# test1.net
KiCad netlist of a schematic drawn in Altium Designer
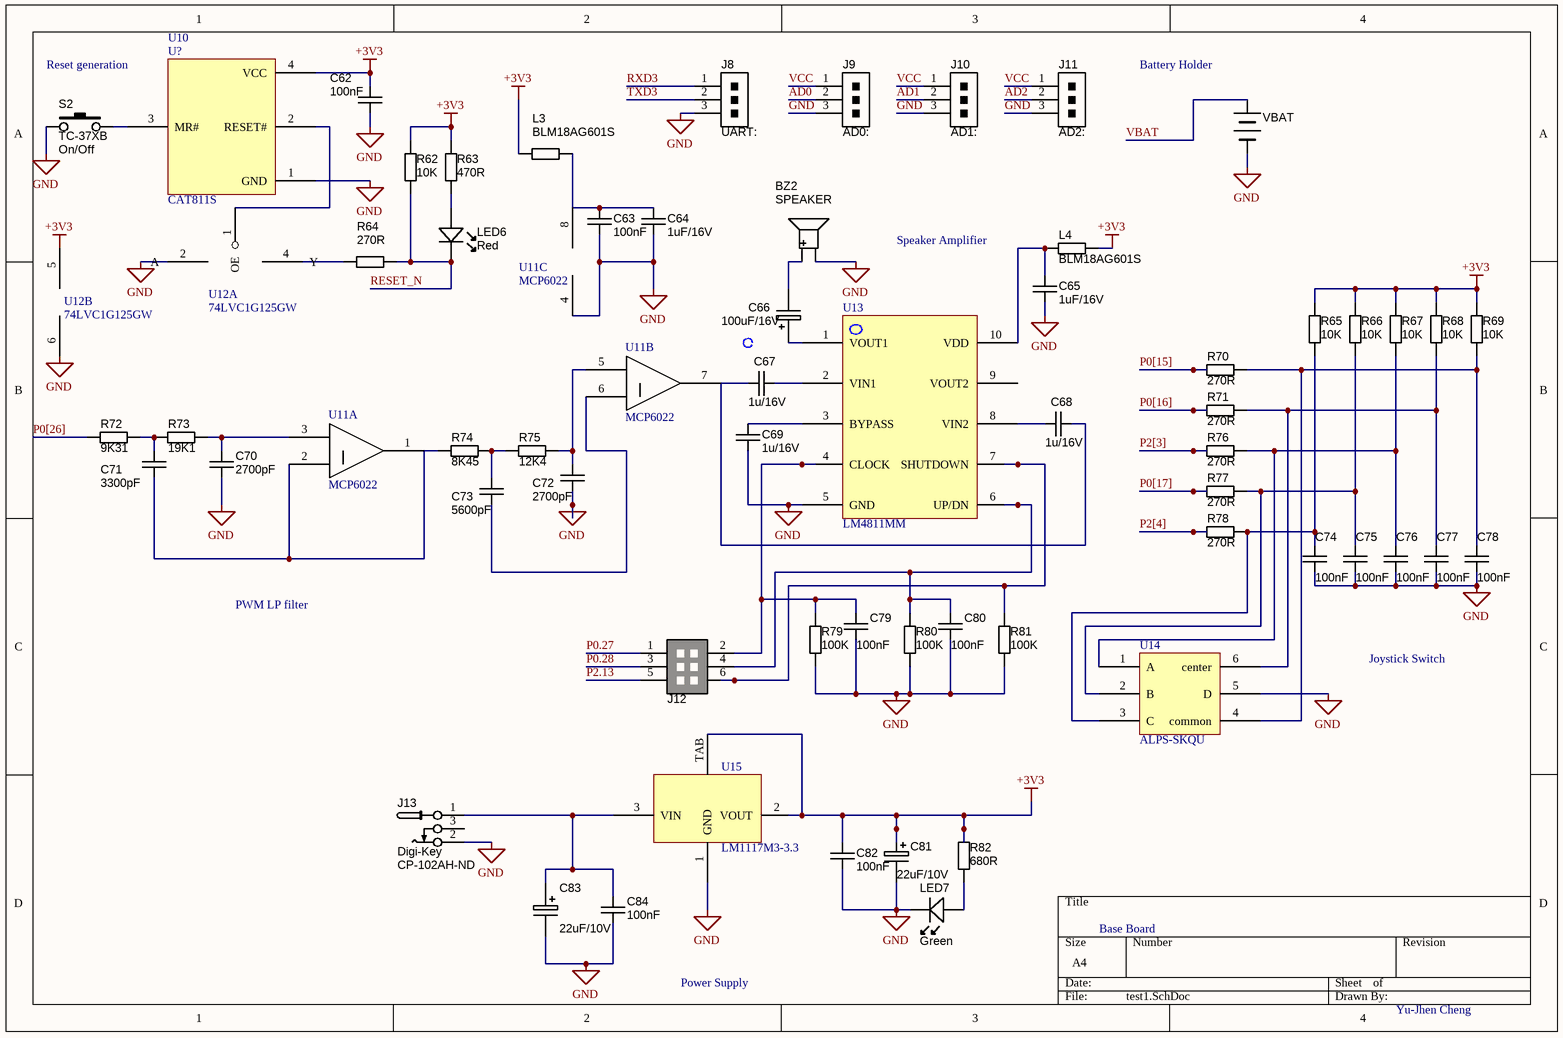
[diagram p0: test1.SchDoc]

(export (version "E")
  (design (tool "Eeschema 10.0.6"))
  (components
    (comp (ref "BZ2")
      (value "Alternate part: 3100-932")
      (footprint "BUZZER_12.0X8.5MM")
      (description "Speaker, Magnetic Transducer")
      (fields (field (name "MANUFACTURER PART NUMBER 1") "SPEAKER"))
      (libsource (lib "PBL - Electromechanical") (part "BZ_12x8.5x6.5_2kHz"))
    )
    (comp (ref "C62")
      (value "100nF")
      (footprint "CAPC2012N")
      (description "Capacitor SMD Cer 100nF 10% 50V X7R 0805")
      (fields (field (name "TOLERANCE") "?0%") (field (name "Comment") "approved sub OK"))
      (libsource (lib "PBL - Capacitors") (part "CAPC_100n_0805"))
    )
    (comp (ref "C63")
      (value "100nF")
      (footprint "CAPC2012N")
      (description "Capacitor SMD Cer 100nF 10% 50V X7R 0805")
      (fields (field (name "TOLERANCE") "?0%") (field (name "Comment") "approved sub OK"))
      (libsource (lib "PBL - Capacitors") (part "CAPC_100n_0805"))
    )
    (comp (ref "C64")
      (value "1uF/16V")
      (footprint "CAPC2012N")
      (description "Capacitor SMD Cer 100nF 10% 50V X7R 0805")
      (fields (field (name "TOLERANCE") "?0%") (field (name "Comment") "approved sub OK"))
      (libsource (lib "PBL - Capacitors") (part "CAPC_100n_0805"))
    )
    (comp (ref "C65")
      (value "1uF/16V")
      (footprint "CAPC2012N")
      (description "Capacitor SMD Cer 100nF 10% 50V X7R 0805")
      (fields (field (name "TOLERANCE") "?0%") (field (name "Comment") "approved sub OK"))
      (libsource (lib "PBL - Capacitors") (part "CAPC_100n_0805"))
    )
    (comp (ref "C66")
      (value "~")
      (footprint "CAPMP3528X210N")
      (description "Capacitor SMD Tantalum 100uF 20% 6.3V 1210")
      (fields (field (name "TOLERANCE") "?0%") (field (name "ALTIUM_UNNAMED_1") "100uF/16V"))
      (libsource (lib "PBL - Capacitors") (part "CAPT_100u_1210_6V3"))
    )
    (comp (ref "C67")
      (value "1u/16V")
      (footprint "CAPC2012N")
      (description "Capacitor SMD Cer 100nF 10% 50V X7R 0805")
      (fields (field (name "TOLERANCE") "?0%") (field (name "Comment") "approved sub OK"))
      (libsource (lib "PBL - Capacitors") (part "CAPC_100n_0805"))
    )
    (comp (ref "C68")
      (value "1u/16V")
      (footprint "CAPC2012N")
      (description "Capacitor SMD Cer 100nF 10% 50V X7R 0805")
      (fields (field (name "TOLERANCE") "?0%") (field (name "Comment") "approved sub OK"))
      (libsource (lib "PBL - Capacitors") (part "CAPC_100n_0805"))
    )
    (comp (ref "C69")
      (value "1u/16V")
      (footprint "CAPC2012N")
      (description "Capacitor SMD Cer 100nF 10% 50V X7R 0805")
      (fields (field (name "TOLERANCE") "?0%") (field (name "Comment") "approved sub OK"))
      (libsource (lib "PBL - Capacitors") (part "CAPC_100n_0805"))
    )
    (comp (ref "C70")
      (value "2700pF")
      (footprint "CAPC2012N")
      (description "Capacitor SMD Cer 100nF 10% 50V X7R 0805")
      (fields (field (name "TOLERANCE") "?0%") (field (name "Comment") "approved sub OK"))
      (libsource (lib "PBL - Capacitors") (part "CAPC_100n_0805"))
    )
    (comp (ref "C71")
      (value "3300pF")
      (footprint "CAPC2012N")
      (description "Capacitor SMD Cer 100nF 10% 50V X7R 0805")
      (fields (field (name "TOLERANCE") "?0%") (field (name "Comment") "approved sub OK"))
      (libsource (lib "PBL - Capacitors") (part "CAPC_100n_0805"))
    )
    (comp (ref "C72")
      (value "2700pF")
      (footprint "CAPC2012N")
      (description "Capacitor SMD Cer 100nF 10% 50V X7R 0805")
      (fields (field (name "TOLERANCE") "?0%") (field (name "Comment") "approved sub OK"))
      (libsource (lib "PBL - Capacitors") (part "CAPC_100n_0805"))
    )
    (comp (ref "C73")
      (value "5600pF")
      (footprint "CAPC2012N")
      (description "Capacitor SMD Cer 100nF 10% 50V X7R 0805")
      (fields (field (name "TOLERANCE") "?0%") (field (name "Comment") "approved sub OK"))
      (libsource (lib "PBL - Capacitors") (part "CAPC_100n_0805"))
    )
    (comp (ref "C74")
      (value "100nF")
      (footprint "CAPC2012N")
      (description "Capacitor SMD Cer 100nF 10% 50V X7R 0805")
      (fields (field (name "TOLERANCE") "?0%") (field (name "Comment") "approved sub OK"))
      (libsource (lib "PBL - Capacitors") (part "CAPC_100n_0805"))
    )
    (comp (ref "C75")
      (value "100nF")
      (footprint "CAPC2012N")
      (description "Capacitor SMD Cer 100nF 10% 50V X7R 0805")
      (fields (field (name "TOLERANCE") "?0%") (field (name "Comment") "approved sub OK"))
      (libsource (lib "PBL - Capacitors") (part "CAPC_100n_0805"))
    )
    (comp (ref "C76")
      (value "100nF")
      (footprint "CAPC2012N")
      (description "Capacitor SMD Cer 100nF 10% 50V X7R 0805")
      (fields (field (name "TOLERANCE") "?0%") (field (name "Comment") "approved sub OK"))
      (libsource (lib "PBL - Capacitors") (part "CAPC_100n_0805"))
    )
    (comp (ref "C77")
      (value "100nF")
      (footprint "CAPC2012N")
      (description "Capacitor SMD Cer 100nF 10% 50V X7R 0805")
      (fields (field (name "TOLERANCE") "?0%") (field (name "Comment") "approved sub OK"))
      (libsource (lib "PBL - Capacitors") (part "CAPC_100n_0805"))
    )
    (comp (ref "C78")
      (value "100nF")
      (footprint "CAPC2012N")
      (description "Capacitor SMD Cer 100nF 10% 50V X7R 0805")
      (fields (field (name "TOLERANCE") "?0%") (field (name "Comment") "approved sub OK"))
      (libsource (lib "PBL - Capacitors") (part "CAPC_100n_0805"))
    )
    (comp (ref "C79")
      (value "100nF")
      (footprint "CAPC2012N")
      (description "Capacitor SMD Cer 100nF 10% 50V X7R 0805")
      (fields (field (name "TOLERANCE") "?0%") (field (name "Comment") "approved sub OK"))
      (libsource (lib "PBL - Capacitors") (part "CAPC_100n_0805"))
    )
    (comp (ref "C80")
      (value "100nF")
      (footprint "CAPC2012N")
      (description "Capacitor SMD Cer 100nF 10% 50V X7R 0805")
      (fields (field (name "TOLERANCE") "?0%") (field (name "Comment") "approved sub OK"))
      (libsource (lib "PBL - Capacitors") (part "CAPC_100n_0805"))
    )
    (comp (ref "C81")
      (value "~")
      (footprint "CAPMP3528X210N")
      (description "Capacitor SMD Tantalum 100uF 20% 6.3V 1210")
      (fields (field (name "TOLERANCE") "?0%") (field (name "ALTIUM_UNNAMED_1") "22uF/10V"))
      (libsource (lib "PBL - Capacitors") (part "CAPT_100u_1210_6V3"))
    )
    (comp (ref "C82")
      (value "100nF")
      (footprint "CAPC2012N")
      (description "Capacitor SMD Cer 100nF 10% 50V X7R 0805")
      (fields (field (name "TOLERANCE") "?0%") (field (name "Comment") "approved sub OK"))
      (libsource (lib "PBL - Capacitors") (part "CAPC_100n_0805"))
    )
    (comp (ref "C83")
      (value "~")
      (footprint "CAPMP3528X210N")
      (description "Capacitor SMD Tantalum 100uF 20% 6.3V 1210")
      (fields (field (name "TOLERANCE") "?0%") (field (name "ALTIUM_UNNAMED_1") "22uF/10V"))
      (libsource (lib "PBL - Capacitors") (part "CAPT_100u_1210_6V3"))
    )
    (comp (ref "C84")
      (value "100nF")
      (footprint "CAPC2012N")
      (description "Capacitor SMD Cer 100nF 10% 50V X7R 0805")
      (fields (field (name "TOLERANCE") "?0%") (field (name "Comment") "approved sub OK"))
      (libsource (lib "PBL - Capacitors") (part "CAPC_100n_0805"))
    )
    (comp (ref "J8")
      (value "CONN_HEADER_1x3P_0.100in")
      (footprint "1x3POS_HEADER")
      (description "Pin Header, THT, Single-row, 2.54mm pitch")
      (libsource (lib "PBL - Connectors") (part "CONN_HEADER_1x3P_0.100in"))
    )
    (comp (ref "J9")
      (value "CONN_HEADER_1x3P_0.100in")
      (footprint "1x3POS_HEADER")
      (description "Pin Header, THT, Single-row, 2.54mm pitch")
      (libsource (lib "PBL - Connectors") (part "CONN_HEADER_1x3P_0.100in"))
    )
    (comp (ref "J10")
      (value "CONN_HEADER_1x3P_0.100in")
      (footprint "1x3POS_HEADER")
      (description "Pin Header, THT, Single-row, 2.54mm pitch")
      (libsource (lib "PBL - Connectors") (part "CONN_HEADER_1x3P_0.100in"))
    )
    (comp (ref "J11")
      (value "CONN_HEADER_1x3P_0.100in")
      (footprint "1x3POS_HEADER")
      (description "Pin Header, THT, Single-row, 2.54mm pitch")
      (libsource (lib "PBL - Connectors") (part "CONN_HEADER_1x3P_0.100in"))
    )
    (comp (ref "J12")
      (value "micro-match socket")
      (footprint "6P_PCB_SOCKET_BRD_MNT_MICRO-MATCH")
      (description "Socket THD 6 POS Double-row 2.54mm pitch")
      (libsource (lib "PBL - Connectors") (part "CONN_SOCKET_2x3P_0.100in_Female"))
    )
    (comp (ref "J13")
      (value "CONN_PWR_JACK_2.1x5.5mm")
      (footprint "CONN_PWR_JACK_2.1x5.5mm")
      (description "Power Connector, THT, 2.1mm ID, 5.5mm OD")
      (fields (field (name "SUPPLIER 1") "Digi-Key") (field (name "SUPPLIER PART NUMBER 1") "CP-102AH-ND"))
      (libsource (lib "PBL - Connectors") (part "CONN_PWR_JACK_2.1x5.5mm"))
    )
    (comp (ref "L3")
      (value "BLM18AG601S")
      (footprint "RESC2012N")
      (description "Resistor SMD chip 10k Ohm 0.125W 5% 0805")
      (fields (field (name "TOLERANCE") "?%") (field (name "Comment") "Thick Film"))
      (libsource (lib "") (part "RES_10K_0805_5%_1"))
    )
    (comp (ref "L4")
      (value "BLM18AG601S")
      (footprint "RESC2012N")
      (description "Resistor SMD chip 10k Ohm 0.125W 5% 0805")
      (fields (field (name "TOLERANCE") "?%") (field (name "Comment") "Thick Film"))
      (libsource (lib "") (part "RES_10K_0805_5%_1"))
    )
    (comp (ref "LED6")
      (value "Red")
      (footprint "LED-0805-A")
      (description "LED, 0805 SMD, Red")
      (libsource (lib "PBL - Light Sources") (part "LED_SMD_Red_0805"))
    )
    (comp (ref "LED7")
      (value "Green")
      (footprint "LED-0805-K")
      (description "LED, 0805 SMD, Green")
      (libsource (lib "PBL - Light Sources") (part "LED_SMD_Green_0805_8mcd"))
    )
    (comp (ref "R62")
      (value "10K")
      (footprint "RESC2012N")
      (description "Resistor SMD chip 10k Ohm 0.125W 5% 0805")
      (fields (field (name "TOLERANCE") "?%") (field (name "Comment") "Thick Film"))
      (libsource (lib "PBL - Resistors") (part "RES_10K_0805_5%"))
    )
    (comp (ref "R63")
      (value "470R")
      (footprint "RESC1608N")
      (description "Resistor SMD chip 470 Ohm 0.1W 5% 0603")
      (fields (field (name "TOLERANCE") "?%") (field (name "Comment") "Thick Film"))
      (libsource (lib "PBL - Resistors") (part "RES_470R_0603_5%"))
    )
    (comp (ref "R64")
      (value "270R")
      (footprint "RESC1005N")
      (description "Resistor SMD chip 330 Ohm 0.063W 5% 0402")
      (fields (field (name "TOLERANCE") "?%") (field (name "Comment") "Thick Film"))
      (libsource (lib "PBL - Resistors") (part "RES_330R_0402_5%"))
    )
    (comp (ref "R65")
      (value "10K")
      (footprint "RESC2012N")
      (description "Resistor SMD chip 10k Ohm 0.125W 5% 0805")
      (fields (field (name "TOLERANCE") "?%") (field (name "Comment") "Thick Film"))
      (libsource (lib "PBL - Resistors") (part "RES_10K_0805_5%"))
    )
    (comp (ref "R66")
      (value "10K")
      (footprint "RESC2012N")
      (description "Resistor SMD chip 10k Ohm 0.125W 5% 0805")
      (fields (field (name "TOLERANCE") "?%") (field (name "Comment") "Thick Film"))
      (libsource (lib "PBL - Resistors") (part "RES_10K_0805_5%"))
    )
    (comp (ref "R67")
      (value "10K")
      (footprint "RESC2012N")
      (description "Resistor SMD chip 10k Ohm 0.125W 5% 0805")
      (fields (field (name "TOLERANCE") "?%") (field (name "Comment") "Thick Film"))
      (libsource (lib "PBL - Resistors") (part "RES_10K_0805_5%"))
    )
    (comp (ref "R68")
      (value "10K")
      (footprint "RESC2012N")
      (description "Resistor SMD chip 10k Ohm 0.125W 5% 0805")
      (fields (field (name "TOLERANCE") "?%") (field (name "Comment") "Thick Film"))
      (libsource (lib "PBL - Resistors") (part "RES_10K_0805_5%"))
    )
    (comp (ref "R69")
      (value "10K")
      (footprint "RESC2012N")
      (description "Resistor SMD chip 10k Ohm 0.125W 5% 0805")
      (fields (field (name "TOLERANCE") "?%") (field (name "Comment") "Thick Film"))
      (libsource (lib "PBL - Resistors") (part "RES_10K_0805_5%"))
    )
    (comp (ref "R70")
      (value "270R")
      (footprint "RESC1005N")
      (description "Resistor SMD chip 330 Ohm 0.063W 5% 0402")
      (fields (field (name "TOLERANCE") "?%") (field (name "Comment") "Thick Film"))
      (libsource (lib "PBL - Resistors") (part "RES_330R_0402_5%"))
    )
    (comp (ref "R71")
      (value "270R")
      (footprint "RESC1005N")
      (description "Resistor SMD chip 330 Ohm 0.063W 5% 0402")
      (fields (field (name "TOLERANCE") "?%") (field (name "Comment") "Thick Film"))
      (libsource (lib "PBL - Resistors") (part "RES_330R_0402_5%"))
    )
    (comp (ref "R72")
      (value "9K31")
      (footprint "RESC1005N")
      (description "Resistor SMD chip 330 Ohm 0.063W 5% 0402")
      (fields (field (name "TOLERANCE") "?%") (field (name "Comment") "Thick Film"))
      (libsource (lib "PBL - Resistors") (part "RES_330R_0402_5%"))
    )
    (comp (ref "R73")
      (value "19K1")
      (footprint "RESC1005N")
      (description "Resistor SMD chip 330 Ohm 0.063W 5% 0402")
      (fields (field (name "TOLERANCE") "?%") (field (name "Comment") "Thick Film"))
      (libsource (lib "PBL - Resistors") (part "RES_330R_0402_5%"))
    )
    (comp (ref "R74")
      (value "8K45")
      (footprint "RESC1005N")
      (description "Resistor SMD chip 330 Ohm 0.063W 5% 0402")
      (fields (field (name "TOLERANCE") "?%") (field (name "Comment") "Thick Film"))
      (libsource (lib "") (part "RES_330R_0402_5%_2"))
    )
    (comp (ref "R75")
      (value "12K4")
      (footprint "RESC1005N")
      (description "Resistor SMD chip 330 Ohm 0.063W 5% 0402")
      (fields (field (name "TOLERANCE") "?%") (field (name "Comment") "Thick Film"))
      (libsource (lib "PBL - Resistors") (part "RES_330R_0402_5%"))
    )
    (comp (ref "R76")
      (value "270R")
      (footprint "RESC1005N")
      (description "Resistor SMD chip 330 Ohm 0.063W 5% 0402")
      (fields (field (name "TOLERANCE") "?%") (field (name "Comment") "Thick Film"))
      (libsource (lib "PBL - Resistors") (part "RES_330R_0402_5%"))
    )
    (comp (ref "R77")
      (value "270R")
      (footprint "RESC1005N")
      (description "Resistor SMD chip 330 Ohm 0.063W 5% 0402")
      (fields (field (name "TOLERANCE") "?%") (field (name "Comment") "Thick Film"))
      (libsource (lib "PBL - Resistors") (part "RES_330R_0402_5%"))
    )
    (comp (ref "R78")
      (value "270R")
      (footprint "RESC1005N")
      (description "Resistor SMD chip 330 Ohm 0.063W 5% 0402")
      (fields (field (name "TOLERANCE") "?%") (field (name "Comment") "Thick Film"))
      (libsource (lib "PBL - Resistors") (part "RES_330R_0402_5%"))
    )
    (comp (ref "R79")
      (value "100K")
      (footprint "RESC1005N")
      (description "Resistor SMD chip 330 Ohm 0.063W 5% 0402")
      (fields (field (name "TOLERANCE") "?%") (field (name "Comment") "Thick Film"))
      (libsource (lib "") (part "RES_330R_0402_5%_1"))
    )
    (comp (ref "R80")
      (value "100K")
      (footprint "RESC1005N")
      (description "Resistor SMD chip 330 Ohm 0.063W 5% 0402")
      (fields (field (name "TOLERANCE") "?%") (field (name "Comment") "Thick Film"))
      (libsource (lib "") (part "RES_330R_0402_5%_1"))
    )
    (comp (ref "R81")
      (value "100K")
      (footprint "RESC1005N")
      (description "Resistor SMD chip 330 Ohm 0.063W 5% 0402")
      (fields (field (name "TOLERANCE") "?%") (field (name "Comment") "Thick Film"))
      (libsource (lib "") (part "RES_330R_0402_5%_1"))
    )
    (comp (ref "R82")
      (value "680R")
      (footprint "RESC1005N")
      (description "Resistor SMD chip 330 Ohm 0.063W 5% 0402")
      (fields (field (name "TOLERANCE") "?%") (field (name "Comment") "Thick Film"))
      (libsource (lib "") (part "RES_330R_0402_5%_1"))
    )
    (comp (ref "S2")
      (value "SW_THT_PB_5.0mm")
      (footprint "SWITCH_TACT-EVQPQxB55")
      (description "Switch, tact, 5.0mm stem")
      (fields (field (name "MANUFACTURER PART NUMBER 1") "TC-37XB") (field (name "FUNCTION") "On/Off"))
      (libsource (lib "PBL - Switches") (part "SW_THT_PB_5.0mm"))
    )
    (comp (ref "U10")
      (value "CAT811S")
      (footprint "SOT-143-RC4_N")
      (libsource (lib "Schlib1") (part "CAT811S"))
    )
    (comp (ref "U11") (value "MCP6022") (footprint "MSOP-UA8_L") (libsource (lib "Schlib1") (part "MCP6022")))
    (comp (ref "U12")
      (value "74LVC1G125GW")
      (footprint "SOT-23-CT5_N")
      (libsource (lib "Schlib1") (part "74LVC1G125GW"))
    )
    (comp (ref "U13")
      (value "LM4811MM")
      (footprint "MSOP-UN10_N")
      (libsource (lib "Schlib1") (part "LM4811MM"))
    )
    (comp (ref "U14")
      (value "ALPS-SKQU")
      (footprint "SOT-23-CH6_L")
      (libsource (lib "Schlib1") (part "ALPS-SKQU"))
    )
    (comp (ref "U15")
      (value "LM1117M3-3.3")
      (footprint "SOT-89-MB3_M")
      (libsource (lib "Schlib1") (part "LM1117M3-3.3"))
    )
    (comp (ref "VBAT")
      (value "~")
      (footprint "PCBComponent_1")
      (description "Battery pack, 2-cell AAA")
      (libsource (lib "PBL - Batteries") (part "BATT_AAAx2_600mAh"))
    )
  )
  (nets
    (net (code "1") (name "+3V3") (class "Default")
      (node (ref "C62") (pin "1") (pintype "passive"))
      (node (ref "C81") (pin "1") (pintype "passive"))
      (node (ref "C82") (pin "2") (pintype "passive"))
      (node (ref "L3") (pin "1") (pinfunction "1_1") (pintype "passive"))
      (node (ref "L4") (pin "2") (pinfunction "2_2") (pintype "passive"))
      (node (ref "R62") (pin "1") (pinfunction "1_1") (pintype "passive"))
      (node (ref "R63") (pin "1") (pinfunction "1_1") (pintype "passive"))
      (node (ref "R65") (pin "1") (pinfunction "1_1") (pintype "passive"))
      (node (ref "R66") (pin "1") (pinfunction "1_1") (pintype "passive"))
      (node (ref "R67") (pin "1") (pinfunction "1_1") (pintype "passive"))
      (node (ref "R68") (pin "1") (pinfunction "1_1") (pintype "passive"))
      (node (ref "R69") (pin "1") (pinfunction "1_1") (pintype "passive"))
      (node (ref "R82") (pin "2") (pinfunction "2_2") (pintype "passive"))
      (node (ref "U10") (pin "4") (pinfunction "VCC_4") (pintype "passive"))
      (node (ref "U15") (pin "2") (pinfunction "VOUT_2") (pintype "passive"))
      (node (ref "U15") (pin "TAB") (pintype "passive"))
    )
    (net (code "2") (name "/AD0") (class "Default")
      (node (ref "J9") (pin "2") (pinfunction "2_2") (pintype "passive"))
    )
    (net (code "3") (name "/AD1") (class "Default")
      (node (ref "J10") (pin "2") (pinfunction "2_2") (pintype "passive"))
    )
    (net (code "4") (name "/AD2") (class "Default")
      (node (ref "J11") (pin "2") (pinfunction "2_2") (pintype "passive"))
    )
    (net (code "5") (name "/P0.27") (class "Default")
      (node (ref "J12") (pin "1") (pinfunction "1_1") (pintype "passive"))
    )
    (net (code "6") (name "/P0.28") (class "Default")
      (node (ref "J12") (pin "3") (pinfunction "3_3") (pintype "passive"))
    )
    (net (code "7") (name "/P0[15]") (class "Default")
      (node (ref "R70") (pin "1") (pinfunction "1_1") (pintype "passive"))
    )
    (net (code "8") (name "/P0[16]") (class "Default")
      (node (ref "R71") (pin "1") (pinfunction "1_1") (pintype "passive"))
    )
    (net (code "9") (name "/P0[17]") (class "Default")
      (node (ref "R77") (pin "1") (pinfunction "1_1") (pintype "passive"))
    )
    (net (code "10") (name "/P0[26]") (class "Default")
      (node (ref "R72") (pin "1") (pinfunction "1_1") (pintype "passive"))
    )
    (net (code "11") (name "/P2.13") (class "Default")
      (node (ref "J12") (pin "5") (pinfunction "5_5") (pintype "passive"))
    )
    (net (code "12") (name "/P2[3]") (class "Default")
      (node (ref "R76") (pin "1") (pinfunction "1_1") (pintype "passive"))
    )
    (net (code "13") (name "/P2[4]") (class "Default")
      (node (ref "R78") (pin "1") (pinfunction "1_1") (pintype "passive"))
    )
    (net (code "14") (name "/RESET_N") (class "Default")
      (node (ref "LED6") (pin "K") (pinfunction "K_K") (pintype "passive"))
      (node (ref "R62") (pin "2") (pinfunction "2_2") (pintype "passive"))
      (node (ref "R64") (pin "2") (pinfunction "2_2") (pintype "passive"))
    )
    (net (code "15") (name "/RXD3") (class "Default")
      (node (ref "J8") (pin "1") (pinfunction "1_1") (pintype "passive"))
    )
    (net (code "16") (name "/TXD3") (class "Default")
      (node (ref "J8") (pin "2") (pinfunction "2_2") (pintype "passive"))
    )
    (net (code "17") (name "/VBAT") (class "Default") (node (ref "VBAT") (pin "1") (pintype "passive")))
    (net (code "18") (name "/VCC") (class "Default")
      (node (ref "J10") (pin "1") (pinfunction "1_1") (pintype "passive"))
      (node (ref "J11") (pin "1") (pinfunction "1_1") (pintype "passive"))
      (node (ref "J9") (pin "1") (pinfunction "1_1") (pintype "passive"))
    )
    (net (code "19") (name "GND") (class "Default")
      (node (ref "BZ2") (pin "2") (pinfunction "Negative_2") (pintype "passive"))
      (node (ref "C62") (pin "2") (pintype "passive"))
      (node (ref "C63") (pin "1") (pintype "passive"))
      (node (ref "C64") (pin "1") (pintype "passive"))
      (node (ref "C65") (pin "1") (pintype "passive"))
      (node (ref "C69") (pin "1") (pintype "passive"))
      (node (ref "C70") (pin "2") (pintype "passive"))
      (node (ref "C72") (pin "2") (pintype "passive"))
      (node (ref "C74") (pin "2") (pintype "passive"))
      (node (ref "C75") (pin "2") (pintype "passive"))
      (node (ref "C76") (pin "2") (pintype "passive"))
      (node (ref "C77") (pin "2") (pintype "passive"))
      (node (ref "C78") (pin "2") (pintype "passive"))
      (node (ref "C79") (pin "2") (pintype "passive"))
      (node (ref "C80") (pin "2") (pintype "passive"))
      (node (ref "C81") (pin "2") (pintype "passive"))
      (node (ref "C82") (pin "1") (pintype "passive"))
      (node (ref "C83") (pin "2") (pintype "passive"))
      (node (ref "C84") (pin "1") (pintype "passive"))
      (node (ref "J10") (pin "3") (pinfunction "3_3") (pintype "passive"))
      (node (ref "J11") (pin "3") (pinfunction "3_3") (pintype "passive"))
      (node (ref "J13") (pin "2") (pinfunction "2_2") (pintype "passive"))
      (node (ref "J8") (pin "3") (pinfunction "3_3") (pintype "passive"))
      (node (ref "J9") (pin "3") (pinfunction "3_3") (pintype "passive"))
      (node (ref "LED7") (pin "K") (pinfunction "K_K") (pintype "passive"))
      (node (ref "R79") (pin "1") (pinfunction "1_1") (pintype "passive"))
      (node (ref "R80") (pin "1") (pinfunction "1_1") (pintype "passive"))
      (node (ref "R81") (pin "1") (pinfunction "1_1") (pintype "passive"))
      (node (ref "S2") (pin "1") (pintype "passive"))
      (node (ref "U10") (pin "1") (pinfunction "GND_1") (pintype "passive"))
      (node (ref "U13") (pin "5") (pinfunction "GND_5") (pintype "passive"))
      (node (ref "U14") (pin "5") (pinfunction "D_5") (pintype "passive"))
      (node (ref "U15") (pin "1") (pinfunction "GND_1") (pintype "passive"))
      (node (ref "VBAT") (pin "2") (pintype "passive"))
    )
    (net (code "20") (name "Net-(BZ2-Positive)") (class "Default")
      (node (ref "BZ2") (pin "1") (pinfunction "Positive_1") (pintype "passive"))
      (node (ref "C66") (pin "2") (pintype "passive"))
    )
    (net (code "21") (name "Net-(C63-Pad2)") (class "Default")
      (node (ref "C63") (pin "2") (pintype "passive"))
      (node (ref "C64") (pin "2") (pintype "passive"))
      (node (ref "L3") (pin "2") (pinfunction "2_2") (pintype "passive"))
    )
    (net (code "22") (name "Net-(C67-Pad1)") (class "Default")
      (node (ref "C67") (pin "1") (pintype "passive"))
      (node (ref "C68") (pin "2") (pintype "passive"))
    )
    (net (code "23") (name "Net-(C70-Pad1)") (class "Default")
      (node (ref "C70") (pin "1") (pintype "passive"))
      (node (ref "R73") (pin "2") (pinfunction "2_2") (pintype "passive"))
    )
    (net (code "24") (name "Net-(C71-Pad1)") (class "Default")
      (node (ref "C71") (pin "1") (pintype "passive"))
      (node (ref "R72") (pin "2") (pinfunction "2_2") (pintype "passive"))
      (node (ref "R73") (pin "1") (pinfunction "1_1") (pintype "passive"))
    )
    (net (code "25") (name "Net-(C71-Pad2)") (class "Default")
      (node (ref "C71") (pin "2") (pintype "passive"))
      (node (ref "R74") (pin "2") (pinfunction "2_2") (pintype "passive"))
    )
    (net (code "26") (name "Net-(C72-Pad1)") (class "Default")
      (node (ref "C72") (pin "1") (pintype "passive"))
      (node (ref "R75") (pin "2") (pinfunction "2_2") (pintype "passive"))
    )
    (net (code "27") (name "Net-(C73-Pad1)") (class "Default")
      (node (ref "C73") (pin "1") (pintype "passive"))
      (node (ref "R74") (pin "1") (pinfunction "1_1") (pintype "passive"))
      (node (ref "R75") (pin "1") (pinfunction "1_1") (pintype "passive"))
    )
    (net (code "28") (name "Net-(LED6-PadA)") (class "Default")
      (node (ref "LED6") (pin "A") (pinfunction "A_A") (pintype "passive"))
      (node (ref "R63") (pin "2") (pinfunction "2_2") (pintype "passive"))
    )
    (net (code "29") (name "Net-(LED7-PadA)") (class "Default")
      (node (ref "LED7") (pin "A") (pinfunction "A_A") (pintype "passive"))
      (node (ref "R82") (pin "1") (pinfunction "1_1") (pintype "passive"))
    )
    (net (code "30") (name "Net-(U10-MR#)") (class "Default")
      (node (ref "S2") (pin "2") (pintype "passive"))
      (node (ref "U10") (pin "3") (pinfunction "MR#_3") (pintype "passive"))
    )
    (net (code "31") (name "Net-(U10-RESET#)") (class "Default")
      (node (ref "U10") (pin "2") (pinfunction "RESET#_2") (pintype "passive"))
      (node (ref "U12") (pin "1") (pinfunction "OE_1") (pintype "passive"))
    )
    (net (code "32") (name "Net-(U13-BYPASS)") (class "Default")
      (node (ref "C69") (pin "2") (pintype "passive"))
      (node (ref "U13") (pin "3") (pinfunction "BYPASS_3") (pintype "passive"))
    )
    (net (code "33") (name "Net-(U13-CLOCK)") (class "Default")
      (node (ref "C79") (pin "1") (pintype "passive"))
      (node (ref "J12") (pin "2") (pinfunction "2_2") (pintype "passive"))
      (node (ref "R79") (pin "2") (pinfunction "2_2") (pintype "passive"))
      (node (ref "U13") (pin "4") (pinfunction "CLOCK_4") (pintype "passive"))
    )
    (net (code "34") (name "Net-(U13-SHUTDOWN)") (class "Default")
      (node (ref "J12") (pin "6") (pinfunction "6_6") (pintype "passive"))
      (node (ref "R81") (pin "2") (pinfunction "2_2") (pintype "passive"))
      (node (ref "U13") (pin "7") (pinfunction "SHUTDOWN_7") (pintype "passive"))
    )
    (net (code "35") (name "Net-(U13-UP{slash}DN)") (class "Default")
      (node (ref "C80") (pin "1") (pintype "passive"))
      (node (ref "J12") (pin "4") (pinfunction "4_4") (pintype "passive"))
      (node (ref "R80") (pin "2") (pinfunction "2_2") (pintype "passive"))
      (node (ref "U13") (pin "6") (pinfunction "UP/DN_6") (pintype "passive"))
    )
    (net (code "36") (name "Net-(U13-VDD)") (class "Default")
      (node (ref "C65") (pin "2") (pintype "passive"))
      (node (ref "L4") (pin "1") (pinfunction "1_1") (pintype "passive"))
      (node (ref "U13") (pin "10") (pinfunction "VDD_10") (pintype "passive"))
    )
    (net (code "37") (name "Net-(U13-VIN1)") (class "Default")
      (node (ref "C67") (pin "2") (pintype "passive"))
      (node (ref "U13") (pin "2") (pinfunction "VIN1_2") (pintype "passive"))
    )
    (net (code "38") (name "Net-(U13-VIN2)") (class "Default")
      (node (ref "C68") (pin "1") (pintype "passive"))
      (node (ref "U13") (pin "8") (pinfunction "VIN2_8") (pintype "passive"))
    )
    (net (code "39") (name "Net-(U13-VOUT1)") (class "Default")
      (node (ref "C66") (pin "1") (pintype "passive"))
      (node (ref "U13") (pin "1") (pinfunction "VOUT1_1") (pintype "passive"))
    )
    (net (code "40") (name "Net-(U14-A)") (class "Default")
      (node (ref "C76") (pin "1") (pintype "passive"))
      (node (ref "R67") (pin "2") (pinfunction "2_2") (pintype "passive"))
      (node (ref "R76") (pin "2") (pinfunction "2_2") (pintype "passive"))
      (node (ref "U14") (pin "1") (pinfunction "A_1") (pintype "passive"))
    )
    (net (code "41") (name "Net-(U14-B)") (class "Default")
      (node (ref "C75") (pin "1") (pintype "passive"))
      (node (ref "R66") (pin "2") (pinfunction "2_2") (pintype "passive"))
      (node (ref "R77") (pin "2") (pinfunction "2_2") (pintype "passive"))
      (node (ref "U14") (pin "2") (pinfunction "B_2") (pintype "passive"))
    )
    (net (code "42") (name "Net-(U14-C)") (class "Default")
      (node (ref "C74") (pin "1") (pintype "passive"))
      (node (ref "R65") (pin "2") (pinfunction "2_2") (pintype "passive"))
      (node (ref "R78") (pin "2") (pinfunction "2_2") (pintype "passive"))
      (node (ref "U14") (pin "3") (pinfunction "C_3") (pintype "passive"))
    )
    (net (code "43") (name "Net-(U14-center)") (class "Default")
      (node (ref "C77") (pin "1") (pintype "passive"))
      (node (ref "R68") (pin "2") (pinfunction "2_2") (pintype "passive"))
      (node (ref "R71") (pin "2") (pinfunction "2_2") (pintype "passive"))
      (node (ref "U14") (pin "6") (pinfunction "center_6") (pintype "passive"))
    )
    (net (code "44") (name "Net-(U14-common)") (class "Default")
      (node (ref "C78") (pin "1") (pintype "passive"))
      (node (ref "R69") (pin "2") (pinfunction "2_2") (pintype "passive"))
      (node (ref "R70") (pin "2") (pinfunction "2_2") (pintype "passive"))
      (node (ref "U14") (pin "4") (pinfunction "common_4") (pintype "passive"))
    )
    (net (code "45") (name "Net-(U15-VIN)") (class "Default")
      (node (ref "C83") (pin "1") (pintype "passive"))
      (node (ref "C84") (pin "2") (pintype "passive"))
      (node (ref "J13") (pin "1") (pinfunction "1_1") (pintype "passive"))
      (node (ref "U15") (pin "3") (pinfunction "VIN_3") (pintype "passive"))
    )
    (net (code "46") (name "unconnected-(C73-Pad2)") (class "Default")
      (node (ref "C73") (pin "2") (pintype "passive"))
    )
    (net (code "47") (name "unconnected-(J13-Pad3)") (class "Default")
      (node (ref "J13") (pin "3") (pinfunction "3_3") (pintype "passive"))
    )
    (net (code "48") (name "unconnected-(R64-Pad1)") (class "Default")
      (node (ref "R64") (pin "1") (pinfunction "1_1") (pintype "passive"))
    )
    (net (code "49") (name "unconnected-(U11A-VINA+-Pad3)") (class "Default")
      (node (ref "U11") (pin "3") (pinfunction "VINA+_3") (pintype "passive"))
    )
    (net (code "50") (name "unconnected-(U11A-VINA--Pad2)") (class "Default")
      (node (ref "U11") (pin "2") (pinfunction "VINA-_2") (pintype "passive"))
    )
    (net (code "51") (name "unconnected-(U11A-VOUTA-Pad1)") (class "Default")
      (node (ref "U11") (pin "1") (pinfunction "VOUTA_1") (pintype "passive"))
    )
    (net (code "52") (name "unconnected-(U11B-VINB+-Pad5)") (class "Default")
      (node (ref "U11") (pin "5") (pinfunction "VINB+_5") (pintype "passive"))
    )
    (net (code "53") (name "unconnected-(U11B-VINB--Pad6)") (class "Default")
      (node (ref "U11") (pin "6") (pinfunction "VINB-_6") (pintype "passive"))
    )
    (net (code "54") (name "unconnected-(U11B-VOUTB-Pad7)") (class "Default")
      (node (ref "U11") (pin "7") (pinfunction "VOUTB_7") (pintype "passive"))
    )
    (net (code "55") (name "unconnected-(U11C-GND-Pad4)") (class "Default")
      (node (ref "U11") (pin "4") (pinfunction "GND_4") (pintype "passive"))
    )
    (net (code "56") (name "unconnected-(U11C-VDD-Pad8)") (class "Default")
      (node (ref "U11") (pin "8") (pinfunction "VDD_8") (pintype "passive"))
    )
    (net (code "57") (name "unconnected-(U12A-A-Pad2)") (class "Default")
      (node (ref "U12") (pin "2") (pinfunction "A_2") (pintype "passive"))
    )
    (net (code "58") (name "unconnected-(U12A-Y-Pad4)") (class "Default")
      (node (ref "U12") (pin "4") (pinfunction "Y_4") (pintype "passive"))
    )
    (net (code "59") (name "unconnected-(U12B-GND-Pad6)") (class "Default")
      (node (ref "U12") (pin "6") (pinfunction "GND_6") (pintype "passive"))
    )
    (net (code "60") (name "unconnected-(U12B-VCC-Pad5)") (class "Default")
      (node (ref "U12") (pin "5") (pinfunction "VCC_5") (pintype "passive"))
    )
    (net (code "61") (name "unconnected-(U13-VOUT2-Pad9)") (class "Default")
      (node (ref "U13") (pin "9") (pinfunction "VOUT2_9") (pintype "passive"))
    )
  )
)
